# dcb_single_channel.net
KiCad netlist of a schematic drawn in Altium Designer
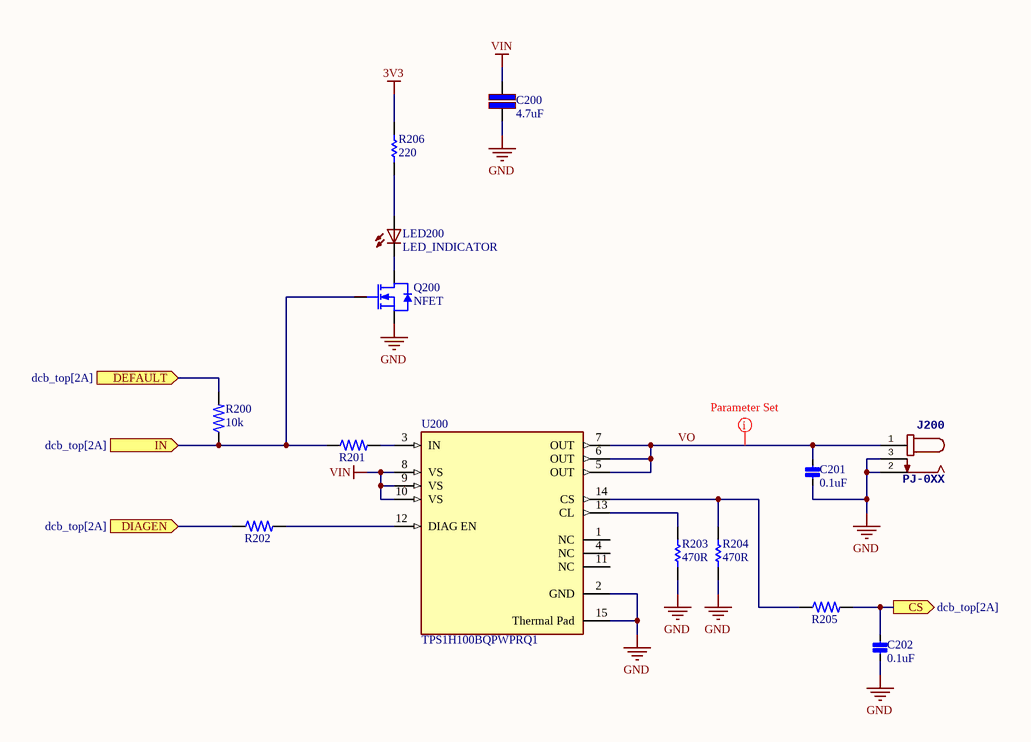
[diagram p0: dcb_single_channel.SchDoc]

(export (version "E")
  (design (tool "Eeschema 10.0.6"))
  (components
    (comp (ref "C200")
      (value "4.7uF")
      (footprint "CAPC3225X20N")
      (description "CAP CER 4.7UF 50V X7R 1210")
      (fields (field (name "VOLTAGE") "50V") (field (name "TOLERANCE") "10%"))
      (libsource (lib "StackFoundry LLC") (part "4.7uF"))
    )
    (comp (ref "C201")
      (value "0.1uF")
      (footprint "FP-CL10-IPC_B")
      (description "Cap Ceramic 0.1uF 50V X7R 20% SMD 0603 125C Paper T/R")
      (fields (field (name "VOLTAGE") "50V") (field (name "Comment") "CAP 0.1uF 50V X7R 0603"))
      (libsource (lib "StackFoundry LLC") (part "C-EU"))
    )
    (comp (ref "C202")
      (value "0.1uF")
      (footprint "FP-CL10-IPC_B")
      (description "Cap Ceramic 0.1uF 50V X7R 20% SMD 0603 125C Paper T/R")
      (fields (field (name "VOLTAGE") "50V") (field (name "Comment") "CAP 0.1uF 50V X7R 0603"))
      (libsource (lib "StackFoundry LLC") (part "C-EU"))
    )
    (comp (ref "J200")
      (value "PJ-0XX")
      (footprint "CUI-PJ-002A_V")
      (description "2.0 x 6.5 mm, 2.5 A, Horizontal, Through Hole, Dc Power Jack Connector")
      (libsource (lib "StackFoundry LLC") (part "Symbol"))
    )
    (comp (ref "LED200")
      (value "LED_INDICATOR")
      (footprint "LED5MM")
      (libsource (lib "StackFoundry LLC") (part "LED_INDICATOR"))
    )
    (comp (ref "Q200")
      (value "NFET")
      (footprint "SOT23-3")
      (libsource (lib "StackFoundry LLC") (part "NFET"))
    )
    (comp (ref "R200")
      (value "10k")
      (footprint "RESC1608-IPC-ML")
      (description "Res General Purpose Thick Film 0603 10K Ohm 1% 1/10W ±100ppm/°C Molded SMD Paper T/R")
      (fields (field (name "Comment") "10K 0603 1%"))
      (libsource (lib "StackFoundry LLC") (part "R-US"))
    )
    (comp (ref "R201")
      (value "4.7k 0603 1%")
      (footprint "RESC1608-IPC-ML")
      (description "RES SMD 4.7K OHM 1% 1/10W 0603")
      (libsource (lib "StackFoundry LLC") (part "R-US"))
    )
    (comp (ref "R202")
      (value "4.7k 0603 1%")
      (footprint "RESC1608-IPC-ML")
      (description "RES SMD 4.7K OHM 1% 1/10W 0603")
      (libsource (lib "StackFoundry LLC") (part "R-US"))
    )
    (comp (ref "R203")
      (value "470R")
      (footprint "RESC2013X60X35LL10T20")
      (description "SMD Chip Resistor, 470 Ohm, ± 1%, 125 mW, 0805 [2012 Metric], Thick Film, General Purpose")
      (fields (field (name "TOLERANCE") "1%") (field (name "Comment") "RC0805FR-07470RL"))
      (libsource (lib "StackFoundry LLC") (part "RES-2"))
    )
    (comp (ref "R204")
      (value "470R")
      (footprint "RESC2013X60X35LL10T20")
      (description "SMD Chip Resistor, 470 Ohm, ± 1%, 125 mW, 0805 [2012 Metric], Thick Film, General Purpose")
      (fields (field (name "TOLERANCE") "1%") (field (name "Comment") "RC0805FR-07470RL"))
      (libsource (lib "StackFoundry LLC") (part "RES-2"))
    )
    (comp (ref "R205")
      (value "4.7k 0603 1%")
      (footprint "RESC1608-IPC-ML")
      (description "RES SMD 4.7K OHM 1% 1/10W 0603")
      (libsource (lib "StackFoundry LLC") (part "R-US"))
    )
    (comp (ref "R206")
      (value "220")
      (footprint "RESC1608-IPC-ML")
      (fields (field (name "TOLERANCE") "5%") (field (name "Comment") "220R 0603 5%"))
      (libsource (lib "StackFoundry LLC") (part "RES-2"))
    )
    (comp (ref "U200")
      (value "TPS1H100BQPWPRQ1")
      (footprint "FP-PWP0014C-IPC_C")
      (description "Current Limit SW 1-IN 1-OUT 5V to 40V 4A Automotive 14-Pin HTSSOP EP T/R")
      (libsource (lib "StackFoundry LLC") (part "9438d576f614b53ae075b99ddcc45f2"))
    )
  )
  (nets
    (net (code "1") (name "/CS") (class "Default")
      (node (ref "C202") (pin "1") (pinfunction "1_1") (pintype "passive"))
      (node (ref "R205") (pin "2") (pinfunction "2_2") (pintype "passive"))
    )
    (net (code "2") (name "/DEFAULT") (class "Default")
      (node (ref "R200") (pin "2") (pinfunction "2_2") (pintype "passive"))
    )
    (net (code "3") (name "/DIAGEN") (class "Default")
      (node (ref "R202") (pin "1") (pinfunction "1_1") (pintype "passive"))
    )
    (net (code "4") (name "/IN") (class "Default")
      (node (ref "Q200") (pin "1") (pinfunction "G_1") (pintype "passive"))
      (node (ref "R200") (pin "1") (pinfunction "1_1") (pintype "passive"))
      (node (ref "R201") (pin "1") (pinfunction "1_1") (pintype "passive"))
    )
    (net (code "5") (name "/VO") (class "Default")
      (node (ref "C201") (pin "1") (pinfunction "1_1") (pintype "passive"))
      (node (ref "J200") (pin "1") (pinfunction "1_1") (pintype "passive"))
      (node (ref "U200") (pin "5") (pinfunction "OUT_5") (pintype "output"))
      (node (ref "U200") (pin "6") (pinfunction "OUT_6") (pintype "output"))
      (node (ref "U200") (pin "7") (pinfunction "OUT_7") (pintype "output"))
    )
    (net (code "6") (name "3V3") (class "Default")
      (node (ref "R206") (pin "2") (pinfunction "2_2") (pintype "passive"))
    )
    (net (code "7") (name "GND") (class "Default")
      (node (ref "C200") (pin "1") (pintype "passive"))
      (node (ref "C201") (pin "2") (pinfunction "2_2") (pintype "passive"))
      (node (ref "C202") (pin "2") (pinfunction "2_2") (pintype "passive"))
      (node (ref "J200") (pin "2") (pinfunction "2_2") (pintype "passive"))
      (node (ref "J200") (pin "3") (pinfunction "3_3") (pintype "passive"))
      (node (ref "Q200") (pin "2") (pinfunction "S_2") (pintype "passive"))
      (node (ref "R203") (pin "1") (pinfunction "1_1") (pintype "passive"))
      (node (ref "R204") (pin "1") (pinfunction "1_1") (pintype "passive"))
      (node (ref "U200") (pin "15") (pinfunction "Thermal_Pad_15") (pintype "passive"))
      (node (ref "U200") (pin "2") (pinfunction "GND_2") (pintype "power_in"))
    )
    (net (code "8") (name "Net-(LED200-PadA)") (class "Default")
      (node (ref "LED200") (pin "A") (pinfunction "A_A") (pintype "passive"))
      (node (ref "R206") (pin "1") (pinfunction "1_1") (pintype "passive"))
    )
    (net (code "9") (name "Net-(Q200-D)") (class "Default")
      (node (ref "LED200") (pin "C") (pinfunction "C_C") (pintype "passive"))
      (node (ref "Q200") (pin "3") (pinfunction "D_3") (pintype "passive"))
    )
    (net (code "10") (name "Net-(U200-CL)") (class "Default")
      (node (ref "R203") (pin "2") (pinfunction "2_2") (pintype "passive"))
      (node (ref "U200") (pin "13") (pinfunction "CL_13") (pintype "output"))
    )
    (net (code "11") (name "Net-(U200-CS)") (class "Default")
      (node (ref "R204") (pin "2") (pinfunction "2_2") (pintype "passive"))
      (node (ref "R205") (pin "1") (pinfunction "1_1") (pintype "passive"))
      (node (ref "U200") (pin "14") (pinfunction "CS_14") (pintype "output"))
    )
    (net (code "12") (name "Net-(U200-DIAG_EN)") (class "Default")
      (node (ref "R202") (pin "2") (pinfunction "2_2") (pintype "passive"))
      (node (ref "U200") (pin "12") (pinfunction "DIAG_EN_12") (pintype "input"))
    )
    (net (code "13") (name "Net-(U200-IN)") (class "Default")
      (node (ref "R201") (pin "2") (pinfunction "2_2") (pintype "passive"))
      (node (ref "U200") (pin "3") (pinfunction "IN_3") (pintype "input"))
    )
    (net (code "14") (name "VIN") (class "Default")
      (node (ref "C200") (pin "2") (pintype "passive"))
      (node (ref "U200") (pin "10") (pinfunction "VS_10") (pintype "input"))
      (node (ref "U200") (pin "8") (pinfunction "VS_8") (pintype "input"))
      (node (ref "U200") (pin "9") (pinfunction "VS_9") (pintype "input"))
    )
    (net (code "15") (name "unconnected-(U200-NC-Pad1)") (class "Default")
      (node (ref "U200") (pin "1") (pinfunction "NC_1") (pintype "passive"))
    )
    (net (code "16") (name "unconnected-(U200-NC-Pad4)") (class "Default")
      (node (ref "U200") (pin "4") (pinfunction "NC_4") (pintype "passive"))
    )
    (net (code "17") (name "unconnected-(U200-NC-Pad11)") (class "Default")
      (node (ref "U200") (pin "11") (pinfunction "NC_11") (pintype "passive"))
    )
  )
)
